# Power.net
KiCad netlist of a schematic drawn in Altium Designer
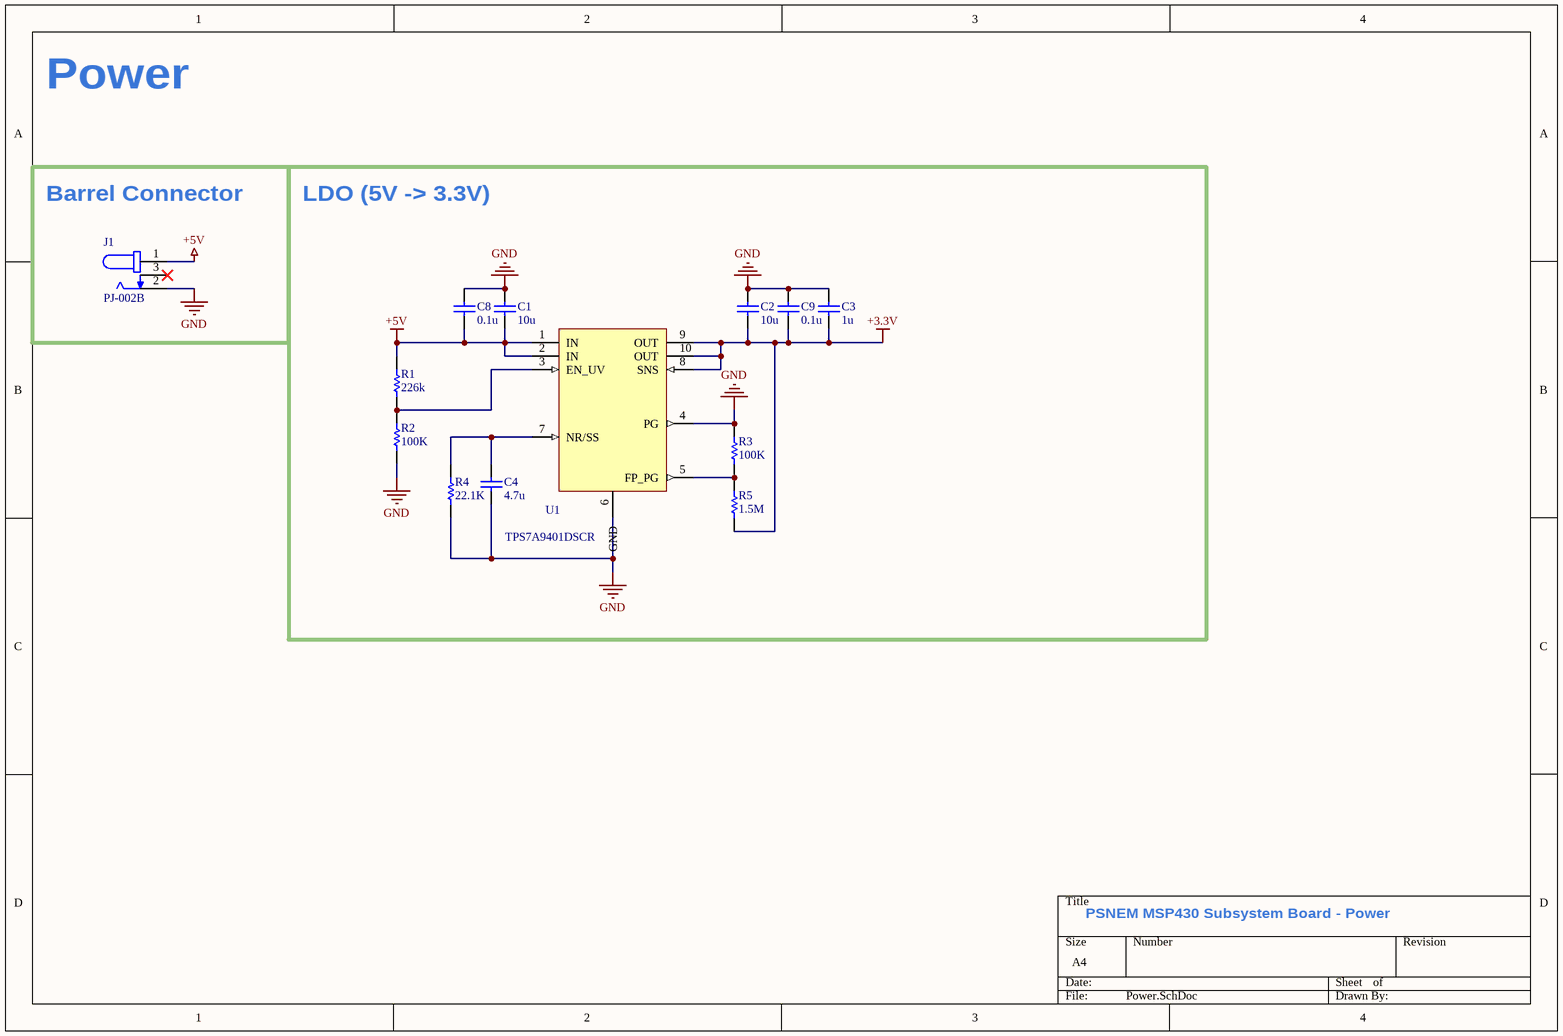
[diagram p0: Power.SchDoc]

(export (version "E")
  (design (tool "Eeschema 10.0.6"))
  (components
    (comp (ref "C1")
      (value "10u")
      (footprint "0805 Cap")
      (description "10 µF ±10% 10V Ceramic Capacitor X7R 0805 (2012 Metric)")
      (libsource (lib "Schlib1") (part "CL21B106KPQNNNE"))
    )
    (comp (ref "C2")
      (value "10u")
      (footprint "0805 Cap")
      (description "10 µF ±10% 10V Ceramic Capacitor X7R 0805 (2012 Metric)")
      (libsource (lib "Schlib1") (part "CL21B106KPQNNNE"))
    )
    (comp (ref "C3")
      (value "1u")
      (footprint "0805 Cap")
      (description "1 µF ±10% 16V Ceramic Capacitor X7R 0805 (2012 Metric)")
      (libsource (lib "Schlib1") (part "CC0805KKX7R7BB105"))
    )
    (comp (ref "C4")
      (value "4.7u")
      (footprint "0805 Cap")
      (description "4.7 µF ±10% 16V Ceramic Capacitor X7R 0805 (2012 Metric)")
      (libsource (lib "Schlib1") (part "CL21B475KOFNFNE"))
    )
    (comp (ref "C8")
      (value "0.1u")
      (footprint "0805 Cap")
      (description "0.1 µF ±10% 50V Ceramic Capacitor X7R 0805 (2012 Metric)")
      (libsource (lib "Schlib1") (part "CC0805KRX7R9BB104"))
    )
    (comp (ref "C9")
      (value "0.1u")
      (footprint "0805 Cap")
      (description "0.1 µF ±10% 50V Ceramic Capacitor X7R 0805 (2012 Metric)")
      (libsource (lib "Schlib1") (part "CC0805KRX7R9BB104"))
    )
    (comp (ref "J1")
      (value "PJ-002B")
      (footprint "PJ-002B")
      (description "Power Barrel Connector Jack 2.50mm ID (0.098\"), 5.50mm OD (0.217\") Through Hole, Right Angle")
      (libsource (lib "Schlib1") (part "PJ-002B"))
    )
    (comp (ref "R1")
      (value "226k")
      (footprint "RESC1608X06N")
      (description "Thin Film Resistors - SMD 226kOhm,0603,0.1%,25")
      (libsource (lib "Schlib1") (part "RN73H1JTTD2263B25"))
    )
    (comp (ref "R2")
      (value "100K")
      (footprint "RESC1608X06N")
      (description "Thin Film Resistors - SMD 0603 0.05% 100Kohm 10ppm SMD")
      (libsource (lib "Schlib1") (part "ERA-3VRW1003V"))
    )
    (comp (ref "R3")
      (value "100K")
      (footprint "RESC1608X06N")
      (description "Thin Film Resistors - SMD 0603 0.05% 100Kohm 10ppm SMD")
      (libsource (lib "Schlib1") (part "ERA-3VRW1003V"))
    )
    (comp (ref "R4")
      (value "22.1K")
      (footprint "RESC1608X06N")
      (description "Thin Film Resistors - SMD 22.1Kohms .1% 25ppm")
      (libsource (lib "Schlib1") (part "TNPW060322K1BEEA"))
    )
    (comp (ref "R5")
      (value "1.5M")
      (footprint "RESC1608X06N")
      (description "Thin Film Resistors - SMD .125W 1.5Mohms .1% 0603 25ppm")
      (libsource (lib "Schlib1") (part "MCT0603MD1504BP500"))
    )
    (comp (ref "U1")
      (value "TPS7A9401DSCR")
      (footprint "TPS7A9401DSCR")
      (description "Linear Voltage Regulator IC Positive Adjustable 1 Output 1A 10-WSON (3x3)")
      (fields (field (name "MANUFACTURER") "Texas Instruments"))
      (libsource (lib "Schlib1") (part "TPS7A9401DSCR"))
    )
  )
  (nets
    (net (code "1") (name "+3.3V") (class "Default")
      (node (ref "C2") (pin "1") (pinfunction "1_1") (pintype "passive"))
      (node (ref "C3") (pin "2") (pinfunction "2_2") (pintype "passive"))
      (node (ref "C9") (pin "1") (pinfunction "1_1") (pintype "passive"))
      (node (ref "R5") (pin "1") (pinfunction "1_1") (pintype "passive"))
      (node (ref "U1") (pin "10") (pinfunction "OUT_10") (pintype "passive"))
      (node (ref "U1") (pin "8") (pinfunction "SNS_8") (pintype "input"))
      (node (ref "U1") (pin "9") (pinfunction "OUT_9") (pintype "passive"))
    )
    (net (code "2") (name "+5V") (class "Default")
      (node (ref "C1") (pin "1") (pinfunction "1_1") (pintype "passive"))
      (node (ref "C8") (pin "2") (pinfunction "2_2") (pintype "passive"))
      (node (ref "J1") (pin "1") (pinfunction "1_1") (pintype "passive"))
      (node (ref "R1") (pin "2") (pinfunction "2_2") (pintype "passive"))
      (node (ref "U1") (pin "1") (pinfunction "IN_1") (pintype "power_in"))
      (node (ref "U1") (pin "2") (pinfunction "IN_2") (pintype "power_in"))
    )
    (net (code "3") (name "GND") (class "Default")
      (node (ref "C1") (pin "2") (pinfunction "2_2") (pintype "passive"))
      (node (ref "C2") (pin "2") (pinfunction "2_2") (pintype "passive"))
      (node (ref "C3") (pin "1") (pinfunction "1_1") (pintype "passive"))
      (node (ref "C4") (pin "1") (pinfunction "1_1") (pintype "passive"))
      (node (ref "C8") (pin "1") (pinfunction "1_1") (pintype "passive"))
      (node (ref "C9") (pin "2") (pinfunction "2_2") (pintype "passive"))
      (node (ref "J1") (pin "2") (pinfunction "2_2") (pintype "passive"))
      (node (ref "R2") (pin "1") (pinfunction "1_1") (pintype "passive"))
      (node (ref "R3") (pin "2") (pinfunction "2_2") (pintype "passive"))
      (node (ref "R4") (pin "1") (pinfunction "1_1") (pintype "passive"))
      (node (ref "U1") (pin "4") (pinfunction "PG_4") (pintype "output"))
    )
    (net (code "4") (name "Net-(U1-EN_UV)") (class "Default")
      (node (ref "R1") (pin "1") (pinfunction "1_1") (pintype "passive"))
      (node (ref "R2") (pin "2") (pinfunction "2_2") (pintype "passive"))
      (node (ref "U1") (pin "3") (pinfunction "EN_UV_3") (pintype "input"))
    )
    (net (code "5") (name "Net-(U1-FP_PG)") (class "Default")
      (node (ref "R3") (pin "1") (pinfunction "1_1") (pintype "passive"))
      (node (ref "R5") (pin "2") (pinfunction "2_2") (pintype "passive"))
      (node (ref "U1") (pin "5") (pinfunction "FP_PG_5") (pintype "output"))
    )
    (net (code "6") (name "Net-(U1-NR{slash}SS)") (class "Default")
      (node (ref "C4") (pin "2") (pinfunction "2_2") (pintype "passive"))
      (node (ref "R4") (pin "2") (pinfunction "2_2") (pintype "passive"))
      (node (ref "U1") (pin "7") (pinfunction "NR/SS_7") (pintype "input"))
    )
    (net (code "7") (name "unconnected-(J1-Pad3)") (class "Default")
      (node (ref "J1") (pin "3") (pinfunction "3_3") (pintype "passive+no_connect"))
    )
    (net (code "8") (name "unconnected-(U1-GND-Pad6)") (class "Default")
      (node (ref "U1") (pin "6") (pinfunction "GND_6") (pintype "power_in"))
    )
  )
)
